# SparkFun_GPS_RTK_Surveyor_-_Enclosure.net
KiCad netlist of a schematic drawn in EAGLE
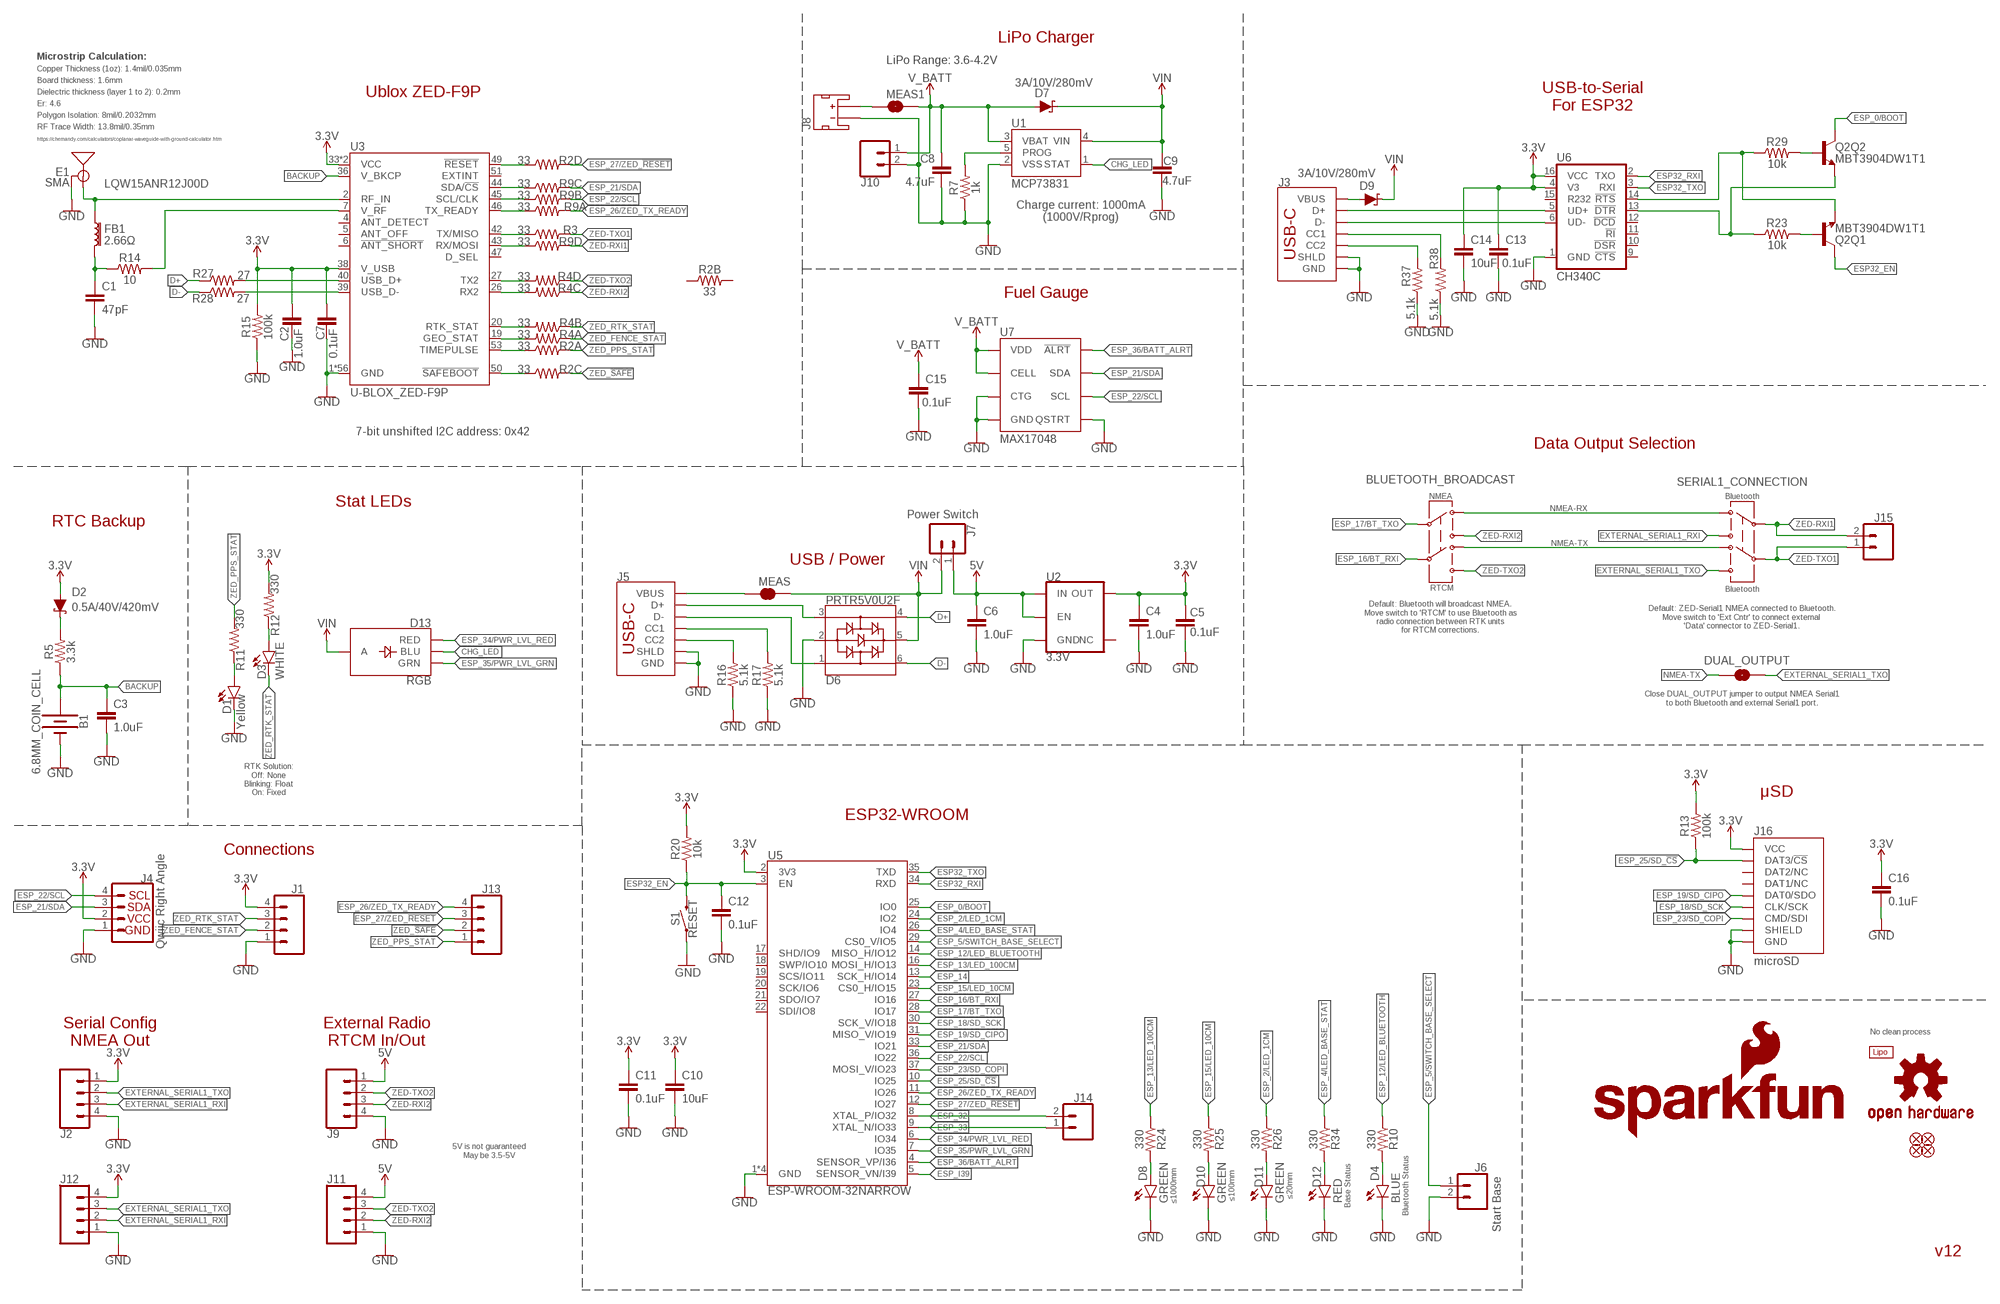
[diagram p0: schematic, sheet 1]

(export (version "E")
  (design (tool "Eeschema 10.0.6"))
  (components
    (comp (ref "B1")
      (value "6.8MM_COIN_CELL")
      (footprint "eagle-import:ML414H_IV01E")
      (libsource (lib "eagle-import") (part "ML414H_IV01E_BATTERY"))
    )
    (comp (ref "BLUETOOTH_BROADCAST")
      (value "SWITCH-DPDT-SMD-AYZ0202")
      (footprint "eagle-import:SWITCH_DPDT_SMD_AYZ0202")
      (libsource (lib "eagle-import") (part "SWITCH-DPDT-SMD-AYZ0202"))
    )
    (comp (ref "BT1")
      (value "LIPO-OUTLINE1100")
      (footprint "eagle-import:LIPO-1000")
      (libsource (lib "eagle-import") (part "LIPO-OUTLINE1100"))
    )
    (comp (ref "C1")
      (value "47pF")
      (footprint "eagle-import:0402")
      (libsource (lib "eagle-import") (part "47PF-0402-25V-5%-X7R"))
    )
    (comp (ref "C2")
      (value "1.0uF")
      (footprint "eagle-import:0603")
      (libsource (lib "eagle-import") (part "1.0UF-0603-16V-10%-X7R"))
    )
    (comp (ref "C3")
      (value "1.0uF")
      (footprint "eagle-import:0603")
      (libsource (lib "eagle-import") (part "1.0UF-0603-16V-10%-X7R"))
    )
    (comp (ref "C4")
      (value "1.0uF")
      (footprint "eagle-import:0603")
      (libsource (lib "eagle-import") (part "1.0UF-0603-16V-10%-X7R"))
    )
    (comp (ref "C5")
      (value "0.1uF")
      (footprint "eagle-import:0603")
      (libsource (lib "eagle-import") (part "0.1UF-0603-25V-5%"))
    )
    (comp (ref "C6")
      (value "1.0uF")
      (footprint "eagle-import:0603")
      (libsource (lib "eagle-import") (part "1.0UF-0603-16V-10%-X7R"))
    )
    (comp (ref "C7")
      (value "0.1uF")
      (footprint "eagle-import:0603")
      (libsource (lib "eagle-import") (part "0.1UF-0603-25V-5%"))
    )
    (comp (ref "C8")
      (value "4.7uF")
      (footprint "eagle-import:0603")
      (libsource (lib "eagle-import") (part "4.7UF-0603-35V-(20%)"))
    )
    (comp (ref "C9")
      (value "4.7uF")
      (footprint "eagle-import:0603")
      (libsource (lib "eagle-import") (part "4.7UF-0603-35V-(20%)"))
    )
    (comp (ref "C10")
      (value "10uF")
      (footprint "eagle-import:0603")
      (libsource (lib "eagle-import") (part "10UF-0603-6.3V-20%"))
    )
    (comp (ref "C11")
      (value "0.1uF")
      (footprint "eagle-import:0603")
      (libsource (lib "eagle-import") (part "0.1UF-0603-25V-(+80/-20%)"))
    )
    (comp (ref "C12")
      (value "0.1uF")
      (footprint "eagle-import:0603")
      (libsource (lib "eagle-import") (part "0.1UF-0603-25V-(+80/-20%)"))
    )
    (comp (ref "C13")
      (value "0.1uF")
      (footprint "eagle-import:0603")
      (libsource (lib "eagle-import") (part "0.1UF-0603-25V-(+80/-20%)"))
    )
    (comp (ref "C14")
      (value "10uF")
      (footprint "eagle-import:0603")
      (libsource (lib "eagle-import") (part "10UF-0603-6.3V-20%"))
    )
    (comp (ref "C15")
      (value "0.1uF")
      (footprint "eagle-import:0603")
      (libsource (lib "eagle-import") (part "0.1UF-0603-25V-(+80/-20%)"))
    )
    (comp (ref "C16")
      (value "0.1uF")
      (footprint "eagle-import:0603")
      (libsource (lib "eagle-import") (part "0.1UF-0603-25V-(+80/-20%)"))
    )
    (comp (ref "D1")
      (value "Yellow")
      (footprint "eagle-import:LED-0603")
      (libsource (lib "eagle-import") (part "LED-YELLOW0603"))
    )
    (comp (ref "D2")
      (value "0.5A/40V/420mV")
      (footprint "eagle-import:SOD-323")
      (libsource (lib "eagle-import") (part "DIODE-SCHOTTKY-PMEG4005EJ"))
    )
    (comp (ref "D3")
      (value "WHITE")
      (footprint "eagle-import:LED-0603")
      (libsource (lib "eagle-import") (part "LED-WHITE0603"))
    )
    (comp (ref "D4")
      (value "BLUE")
      (footprint "eagle-import:LED-0603")
      (libsource (lib "eagle-import") (part "LED-BLUE0603"))
    )
    (comp (ref "D6")
      (value "PRTR5V0U2F")
      (footprint "eagle-import:SOT886")
      (libsource (lib "eagle-import") (part "PRTR5V0U2F"))
    )
    (comp (ref "D7")
      (value "3A/10V/280mV")
      (footprint "eagle-import:SOD-323")
      (libsource (lib "eagle-import") (part "DIODE-SCHOTTKY-BAT60A"))
    )
    (comp (ref "D8")
      (value "GREEN")
      (footprint "eagle-import:LED-0603")
      (libsource (lib "eagle-import") (part "LED-GREEN0603"))
    )
    (comp (ref "D9")
      (value "3A/10V/280mV")
      (footprint "eagle-import:SOD-323")
      (libsource (lib "eagle-import") (part "DIODE-SCHOTTKY-BAT60A"))
    )
    (comp (ref "D10")
      (value "GREEN")
      (footprint "eagle-import:LED-0603")
      (libsource (lib "eagle-import") (part "LED-GREEN0603"))
    )
    (comp (ref "D11")
      (value "GREEN")
      (footprint "eagle-import:LED-0603")
      (libsource (lib "eagle-import") (part "LED-GREEN0603"))
    )
    (comp (ref "D12")
      (value "RED")
      (footprint "eagle-import:LED-0603")
      (libsource (lib "eagle-import") (part "LED-RED0603"))
    )
    (comp (ref "D13")
      (value "RGB")
      (footprint "eagle-import:P-LCC-4-3")
      (libsource (lib "eagle-import") (part "LED-RGB-CAPLCC"))
    )
    (comp (ref "DUAL_OUTPUT")
      (value "JUMPER-SMT_2_NO_SILK")
      (footprint "eagle-import:SMT-JUMPER_2_NO_SILK")
      (libsource (lib "eagle-import") (part "JUMPER-SMT_2_NO_SILK"))
    )
    (comp (ref "E1")
      (value "SMA")
      (footprint "eagle-import:SMA-EDGE-SMD")
      (libsource (lib "eagle-import") (part "ANTENNA-GROUNDEDEDGE_SMA_SMD"))
    )
    (comp (ref "FB1")
      (value "2.66Ω")
      (footprint "eagle-import:0402-TIGHT")
      (libsource (lib "eagle-import") (part "FERRITE_BEAD-0402-2.66OHM-1GHZ"))
    )
    (comp (ref "J1")
      (value "CONN_041X04_NO_SILK_NO_POP")
      (footprint "eagle-import:1X04_NO_SILK")
      (libsource (lib "eagle-import") (part "CONN_041X04_NO_SILK_NO_POP"))
    )
    (comp (ref "J2")
      (value "CONN_04JST-SMD-LOCKING")
      (footprint "eagle-import:JST-4-SMD-1.25MM-LOCKING")
      (libsource (lib "eagle-import") (part "CONN_04JST-SMD-LOCKING"))
    )
    (comp (ref "J3")
      (value "USB-C")
      (footprint "eagle-import:USB-C-16P-2LAYER-PADS")
      (libsource (lib "eagle-import") (part "USB_C_2-LAYER_PADS"))
    )
    (comp (ref "J4")
      (value "Qwiic Right Angle")
      (footprint "eagle-import:JST04_1MM_RA")
      (libsource (lib "eagle-import") (part "I2C_STANDARDQWIIC"))
    )
    (comp (ref "J5")
      (value "USB_C_2-LAYER_PADS")
      (footprint "eagle-import:USB-C-16P-2LAYER-PADS")
      (libsource (lib "eagle-import") (part "USB_C_2-LAYER_PADS"))
    )
    (comp (ref "J6")
      (value "Start Base")
      (footprint "eagle-import:JST-2-SMD")
      (libsource (lib "eagle-import") (part "CONN_02-JST-2MM-SMT"))
    )
    (comp (ref "J7")
      (value "Power Switch")
      (footprint "eagle-import:JST-2-SMD")
      (libsource (lib "eagle-import") (part "CONN_02-JST-2MM-SMT"))
    )
    (comp (ref "J8")
      (value "JST_2MM_MALE")
      (footprint "eagle-import:JST-2-SMD")
      (libsource (lib "eagle-import") (part "JST_2MM_MALE"))
    )
    (comp (ref "J9")
      (value "CONN_04JST-SMD-LOCKING")
      (footprint "eagle-import:JST-4-SMD-1.25MM-LOCKING")
      (libsource (lib "eagle-import") (part "CONN_04JST-SMD-LOCKING"))
    )
    (comp (ref "J10")
      (value "CONN_021X02_NO_SILK")
      (footprint "eagle-import:1X02_NO_SILK")
      (libsource (lib "eagle-import") (part "CONN_021X02_NO_SILK"))
    )
    (comp (ref "J11")
      (value "CONN_041X04_NO_SILK_NO_POP")
      (footprint "eagle-import:1X04_NO_SILK")
      (libsource (lib "eagle-import") (part "CONN_041X04_NO_SILK_NO_POP"))
    )
    (comp (ref "J12")
      (value "CONN_041X04_NO_SILK_NO_POP")
      (footprint "eagle-import:1X04_NO_SILK")
      (libsource (lib "eagle-import") (part "CONN_041X04_NO_SILK_NO_POP"))
    )
    (comp (ref "J13")
      (value "CONN_041X04_NO_SILK_NO_POP")
      (footprint "eagle-import:1X04_NO_SILK")
      (libsource (lib "eagle-import") (part "CONN_041X04_NO_SILK_NO_POP"))
    )
    (comp (ref "J14")
      (value "CONN_021X02_NO_SILK")
      (footprint "eagle-import:1X02_NO_SILK")
      (libsource (lib "eagle-import") (part "CONN_021X02_NO_SILK"))
    )
    (comp (ref "J15")
      (value "CONN_021X02_NO_SILK")
      (footprint "eagle-import:1X02_NO_SILK")
      (libsource (lib "eagle-import") (part "CONN_021X02_NO_SILK"))
    )
    (comp (ref "J16")
      (value "microSD")
      (footprint "eagle-import:MICRO-SD-SOCKET")
      (libsource (lib "eagle-import") (part "MICRO-SD-SDIOPUSH-PUSH"))
    )
    (comp (ref "JP21")
      (value "FIDUCIALUFIDUCIAL")
      (footprint "eagle-import:FIDUCIAL-MICRO")
      (libsource (lib "eagle-import") (part "FIDUCIALUFIDUCIAL"))
    )
    (comp (ref "JP61")
      (value "FIDUCIALUFIDUCIAL")
      (footprint "eagle-import:FIDUCIAL-MICRO")
      (libsource (lib "eagle-import") (part "FIDUCIALUFIDUCIAL"))
    )
    (comp (ref "JP71")
      (value "FIDUCIALUFIDUCIAL")
      (footprint "eagle-import:FIDUCIAL-MICRO")
      (libsource (lib "eagle-import") (part "FIDUCIALUFIDUCIAL"))
    )
    (comp (ref "JP81")
      (value "FIDUCIALUFIDUCIAL")
      (footprint "eagle-import:FIDUCIAL-MICRO")
      (libsource (lib "eagle-import") (part "FIDUCIALUFIDUCIAL"))
    )
    (comp (ref "LOGO1")
      (value "OSHW-LOGOMINI")
      (footprint "eagle-import:OSHW-LOGO-MINI")
      (libsource (lib "eagle-import") (part "OSHW-LOGOMINI"))
    )
    (comp (ref "LOGO2")
      (value "SFE_LOGO_NAME_FLAME.1_INCH")
      (footprint "eagle-import:SFE_LOGO_NAME_FLAME_.1")
      (libsource (lib "eagle-import") (part "SFE_LOGO_NAME_FLAME.1_INCH"))
    )
    (comp (ref "MEAS")
      (value "JUMPER-COMBO_2_NC_TRACE")
      (footprint "eagle-import:COMBO-JUMPER_2_NC_TRACE")
      (libsource (lib "eagle-import") (part "JUMPER-COMBO_2_NC_TRACE"))
    )
    (comp (ref "MEAS1")
      (value "JUMPER-COMBO_2_NC_TRACE")
      (footprint "eagle-import:COMBO-JUMPER_2_NC_TRACE")
      (libsource (lib "eagle-import") (part "JUMPER-COMBO_2_NC_TRACE"))
    )
    (comp (ref "Q2")
      (value "MBT3904DW1T1")
      (footprint "eagle-import:SC70-6")
      (libsource (lib "eagle-import") (part "TRANS_NPN_DUAL-MBT3904DW1T1"))
    )
    (comp (ref "R2")
      (value "33")
      (footprint "eagle-import:1206_RA")
      (libsource (lib "eagle-import") (part "33OHM_RA-1206-1/16W-5%"))
    )
    (comp (ref "R3")
      (value "33")
      (footprint "eagle-import:0603")
      (libsource (lib "eagle-import") (part "33OHM-0603-1/10W-1%"))
    )
    (comp (ref "R4")
      (value "33")
      (footprint "eagle-import:1206_RA")
      (libsource (lib "eagle-import") (part "33OHM_RA-1206-1/16W-5%"))
    )
    (comp (ref "R5")
      (value "3.3k")
      (footprint "eagle-import:0603")
      (libsource (lib "eagle-import") (part "3.3KOHM-0603-1/10W-1%"))
    )
    (comp (ref "R7")
      (value "1k")
      (footprint "eagle-import:0603")
      (libsource (lib "eagle-import") (part "1KOHM-0603-1/10W-1%"))
    )
    (comp (ref "R9")
      (value "33")
      (footprint "eagle-import:1206_RA")
      (libsource (lib "eagle-import") (part "33OHM_RA-1206-1/16W-5%"))
    )
    (comp (ref "R10")
      (value "330")
      (footprint "eagle-import:0603")
      (libsource (lib "eagle-import") (part "330OHM-0603-1/10W-1%"))
    )
    (comp (ref "R11")
      (value "330")
      (footprint "eagle-import:0603")
      (libsource (lib "eagle-import") (part "330OHM-0603-1/10W-1%"))
    )
    (comp (ref "R12")
      (value "330")
      (footprint "eagle-import:0603")
      (libsource (lib "eagle-import") (part "330OHM-0603-1/10W-1%"))
    )
    (comp (ref "R13")
      (value "100k")
      (footprint "eagle-import:0603")
      (libsource (lib "eagle-import") (part "100KOHM-0603-1/10W-1%"))
    )
    (comp (ref "R14")
      (value "10")
      (footprint "eagle-import:0603")
      (libsource (lib "eagle-import") (part "10OHM-0603-1/10W-1%"))
    )
    (comp (ref "R15")
      (value "100k")
      (footprint "eagle-import:0603")
      (libsource (lib "eagle-import") (part "100KOHM-0603-1/10W-1%"))
    )
    (comp (ref "R16")
      (value "5.1k")
      (footprint "eagle-import:0603")
      (libsource (lib "eagle-import") (part "5.1KOHM5.1KOHM-0603-1/10W-1%"))
    )
    (comp (ref "R17")
      (value "5.1k")
      (footprint "eagle-import:0603")
      (libsource (lib "eagle-import") (part "5.1KOHM5.1KOHM-0603-1/10W-1%"))
    )
    (comp (ref "R20")
      (value "10k")
      (footprint "eagle-import:0603")
      (libsource (lib "eagle-import") (part "10KOHM-0603-1/10W-1%"))
    )
    (comp (ref "R23")
      (value "10k")
      (footprint "eagle-import:0603")
      (libsource (lib "eagle-import") (part "10KOHM-0603-1/10W-1%"))
    )
    (comp (ref "R24")
      (value "330")
      (footprint "eagle-import:0603")
      (libsource (lib "eagle-import") (part "330OHM-0603-1/10W-1%"))
    )
    (comp (ref "R25")
      (value "330")
      (footprint "eagle-import:0603")
      (libsource (lib "eagle-import") (part "330OHM-0603-1/10W-1%"))
    )
    (comp (ref "R26")
      (value "330")
      (footprint "eagle-import:0603")
      (libsource (lib "eagle-import") (part "330OHM-0603-1/10W-1%"))
    )
    (comp (ref "R27")
      (value "27")
      (footprint "eagle-import:0603")
      (libsource (lib "eagle-import") (part "27OHM-0603-1/10W-1%"))
    )
    (comp (ref "R28")
      (value "27")
      (footprint "eagle-import:0603")
      (libsource (lib "eagle-import") (part "27OHM-0603-1/10W-1%"))
    )
    (comp (ref "R29")
      (value "10k")
      (footprint "eagle-import:0603")
      (libsource (lib "eagle-import") (part "10KOHM-0603-1/10W-1%"))
    )
    (comp (ref "R34")
      (value "330")
      (footprint "eagle-import:0603")
      (libsource (lib "eagle-import") (part "330OHM-0603-1/10W-1%"))
    )
    (comp (ref "R37")
      (value "5.1k")
      (footprint "eagle-import:0603")
      (libsource (lib "eagle-import") (part "5.1KOHM5.1KOHM-0603-1/10W-1%"))
    )
    (comp (ref "R38")
      (value "5.1k")
      (footprint "eagle-import:0603")
      (libsource (lib "eagle-import") (part "5.1KOHM5.1KOHM-0603-1/10W-1%"))
    )
    (comp (ref "S1")
      (value "RESET")
      (footprint "eagle-import:TACTILE_SWITCH_SMD_5.2MM")
      (libsource (lib "eagle-import") (part "MOMENTARY-SWITCH-SPST-SMD-5.2-TALL-REDUNDANT"))
    )
    (comp (ref "SERIAL1_CONNECTION")
      (value "SWITCH-DPDT-SMD-AYZ0202")
      (footprint "eagle-import:SWITCH_DPDT_SMD_AYZ0202")
      (libsource (lib "eagle-import") (part "SWITCH-DPDT-SMD-AYZ0202"))
    )
    (comp (ref "U1")
      (value "MCP73831")
      (footprint "eagle-import:SOT23-5")
      (libsource (lib "eagle-import") (part "MCP73831"))
    )
    (comp (ref "U2")
      (value "3.3V")
      (footprint "eagle-import:SOT23-5")
      (libsource (lib "eagle-import") (part "V_REG_AP2112K-3.3V"))
    )
    (comp (ref "U3")
      (value "U-BLOX_ZED-F9P")
      (footprint "eagle-import:ZED-F9P")
      (libsource (lib "eagle-import") (part "U-BLOX_ZED-F9P"))
    )
    (comp (ref "U5")
      (value "ESP-WROOM-32NARROW")
      (footprint "eagle-import:ESP-WROOM-32-NARROW")
      (libsource (lib "eagle-import") (part "ESP-WROOM-32NARROW"))
    )
    (comp (ref "U6")
      (value "CH340C")
      (footprint "eagle-import:SO016")
      (libsource (lib "eagle-import") (part "CH340C"))
    )
    (comp (ref "U7")
      (value "MAX17048")
      (footprint "eagle-import:DFN-8")
      (libsource (lib "eagle-import") (part "MAX17048DFN8"))
    )
  )
  (nets
    (net (code "1") (name "3.3V") (class "Default")
      (node (ref "C10") (pin "1") (pinfunction "1_1") (pintype "passive"))
      (node (ref "C11") (pin "1") (pinfunction "1_1") (pintype "passive"))
      (node (ref "C13") (pin "1") (pinfunction "1_1") (pintype "passive"))
      (node (ref "C14") (pin "1") (pinfunction "1_1") (pintype "passive"))
      (node (ref "C16") (pin "1") (pinfunction "1_1") (pintype "passive"))
      (node (ref "C2") (pin "1") (pinfunction "1_1") (pintype "passive"))
      (node (ref "C4") (pin "1") (pinfunction "1_1") (pintype "passive"))
      (node (ref "C5") (pin "2") (pinfunction "2_2") (pintype "passive"))
      (node (ref "C7") (pin "2") (pinfunction "2_2") (pintype "passive"))
      (node (ref "D2") (pin "A") (pinfunction "A_A") (pintype "passive"))
      (node (ref "J1") (pin "4") (pinfunction "4_4") (pintype "passive"))
      (node (ref "J12") (pin "4") (pinfunction "4_4") (pintype "passive"))
      (node (ref "J16") (pin "VCC") (pinfunction "VCC_VCC") (pintype "bidirectional"))
      (node (ref "J2") (pin "1") (pinfunction "1_1") (pintype "passive"))
      (node (ref "J4") (pin "2") (pinfunction "2_2") (pintype "power_in"))
      (node (ref "R12") (pin "2") (pinfunction "2_2") (pintype "passive"))
      (node (ref "R13") (pin "2") (pinfunction "2_2") (pintype "passive"))
      (node (ref "R15") (pin "2") (pinfunction "2_2") (pintype "passive"))
      (node (ref "R20") (pin "2") (pinfunction "2_2") (pintype "passive"))
      (node (ref "U2") (pin "5") (pinfunction "OUT_5") (pintype "passive"))
      (node (ref "U3") (pin "33") (pinfunction "VCC_33") (pintype "bidirectional"))
      (node (ref "U3") (pin "34") (pinfunction "VCC_34") (pintype "bidirectional"))
      (node (ref "U3") (pin "38") (pinfunction "V_USB_38") (pintype "bidirectional"))
      (node (ref "U5") (pin "2") (pinfunction "3V3_2") (pintype "bidirectional"))
      (node (ref "U6") (pin "16") (pinfunction "VCC_16") (pintype "bidirectional"))
      (node (ref "U6") (pin "4") (pinfunction "V3_4") (pintype "bidirectional"))
    )
    (net (code "2") (name "5V") (class "Default")
      (node (ref "C6") (pin "1") (pinfunction "1_1") (pintype "passive"))
      (node (ref "J11") (pin "4") (pinfunction "4_4") (pintype "passive"))
      (node (ref "J7") (pin "1") (pinfunction "2_1") (pintype "passive"))
      (node (ref "J9") (pin "1") (pinfunction "1_1") (pintype "passive"))
      (node (ref "U2") (pin "1") (pinfunction "IN_1") (pintype "input"))
      (node (ref "U2") (pin "3") (pinfunction "EN_3") (pintype "input"))
    )
    (net (code "3") (name "BACKUP") (class "Default")
      (node (ref "B1") (pin "+") (pinfunction "+_+") (pintype "power_in"))
      (node (ref "C3") (pin "1") (pinfunction "1_1") (pintype "passive"))
      (node (ref "R5") (pin "1") (pinfunction "1_1") (pintype "passive"))
      (node (ref "U3") (pin "36") (pinfunction "V_BKCP_36") (pintype "bidirectional"))
    )
    (net (code "4") (name "CHG_LED") (class "Default")
      (node (ref "D13") (pin "3") (pinfunction "BLU_3") (pintype "bidirectional"))
      (node (ref "U1") (pin "1") (pinfunction "STAT_1") (pintype "output"))
    )
    (net (code "5") (name "D+") (class "Default")
      (node (ref "D6") (pin "4") (pinfunction "4_4") (pintype "bidirectional"))
      (node (ref "R27") (pin "1") (pinfunction "1_1") (pintype "passive"))
    )
    (net (code "6") (name "D-") (class "Default")
      (node (ref "D6") (pin "6") (pinfunction "6_6") (pintype "bidirectional"))
      (node (ref "R28") (pin "1") (pinfunction "1_1") (pintype "passive"))
    )
    (net (code "7") (name "ESP32_EN") (class "Default")
      (node (ref "C12") (pin "1") (pinfunction "1_1") (pintype "passive"))
      (node (ref "Q2") (pin "3") (pinfunction "C_3") (pintype "passive"))
      (node (ref "R20") (pin "1") (pinfunction "1_1") (pintype "passive"))
      (node (ref "S1") (pin "3") (pinfunction "2_3") (pintype "passive"))
      (node (ref "S1") (pin "4") (pinfunction "2_4") (pintype "passive"))
      (node (ref "U5") (pin "3") (pinfunction "EN_3") (pintype "bidirectional"))
    )
    (net (code "8") (name "ESP32_RXI") (class "Default")
      (node (ref "U5") (pin "34") (pinfunction "RXD_34") (pintype "bidirectional"))
      (node (ref "U6") (pin "2") (pinfunction "TXO_2") (pintype "bidirectional"))
    )
    (net (code "9") (name "ESP32_TXO") (class "Default")
      (node (ref "U5") (pin "35") (pinfunction "TXD_35") (pintype "bidirectional"))
      (node (ref "U6") (pin "3") (pinfunction "RXI_3") (pintype "bidirectional"))
    )
    (net (code "10") (name "ESP_0{slash}BOOT") (class "Default")
      (node (ref "Q2") (pin "6") (pinfunction "C_6") (pintype "passive"))
      (node (ref "U5") (pin "25") (pinfunction "IO0_25") (pintype "bidirectional"))
    )
    (net (code "11") (name "ESP_2{slash}LED_1CM") (class "Default")
      (node (ref "R26") (pin "1") (pinfunction "1_1") (pintype "passive"))
      (node (ref "U5") (pin "24") (pinfunction "IO2_24") (pintype "bidirectional"))
    )
    (net (code "12") (name "ESP_4{slash}LED_BASE_STAT") (class "Default")
      (node (ref "R34") (pin "1") (pinfunction "1_1") (pintype "passive"))
      (node (ref "U5") (pin "26") (pinfunction "IO4_26") (pintype "bidirectional"))
    )
    (net (code "13") (name "ESP_5{slash}SWITCH_BASE_SELECT") (class "Default")
      (node (ref "J6") (pin "1") (pinfunction "2_1") (pintype "passive"))
      (node (ref "U5") (pin "29") (pinfunction "CS0_V/IO5_29") (pintype "bidirectional"))
    )
    (net (code "14") (name "ESP_12{slash}LED_BLUETOOTH") (class "Default")
      (node (ref "R10") (pin "1") (pinfunction "1_1") (pintype "passive"))
      (node (ref "U5") (pin "14") (pinfunction "MISO_H/IO12_14") (pintype "bidirectional"))
    )
    (net (code "15") (name "ESP_13{slash}LED_100CM") (class "Default")
      (node (ref "R24") (pin "1") (pinfunction "1_1") (pintype "passive"))
      (node (ref "U5") (pin "16") (pinfunction "MOSI_H/IO13_16") (pintype "bidirectional"))
    )
    (net (code "16") (name "ESP_14") (class "Default")
      (node (ref "U5") (pin "13") (pinfunction "SCK_H/IO14_13") (pintype "bidirectional"))
    )
    (net (code "17") (name "ESP_15{slash}LED_10CM") (class "Default")
      (node (ref "R25") (pin "1") (pinfunction "1_1") (pintype "passive"))
      (node (ref "U5") (pin "23") (pinfunction "CS0_H/IO15_23") (pintype "bidirectional"))
    )
    (net (code "18") (name "ESP_16{slash}BT_RXI") (class "Default")
      (node (ref "BLUETOOTH_BROADCAST") (pin "5") (pinfunction "5_5") (pintype "bidirectional"))
      (node (ref "U5") (pin "27") (pinfunction "IO16_27") (pintype "bidirectional"))
    )
    (net (code "19") (name "ESP_17{slash}BT_TXO") (class "Default")
      (node (ref "BLUETOOTH_BROADCAST") (pin "2") (pinfunction "2_2") (pintype "bidirectional"))
      (node (ref "U5") (pin "28") (pinfunction "IO17_28") (pintype "bidirectional"))
    )
    (net (code "20") (name "ESP_18{slash}SD_SCK") (class "Default")
      (node (ref "J16") (pin "SCLK") (pinfunction "CLK/SCK_SCLK") (pintype "bidirectional"))
      (node (ref "U5") (pin "30") (pinfunction "SCK_V/IO18_30") (pintype "bidirectional"))
    )
    (net (code "21") (name "ESP_19{slash}SD_CIPO") (class "Default")
      (node (ref "J16") (pin "DO/DAT0") (pinfunction "DAT0/SDO_DO/DAT0") (pintype "bidirectional"))
      (node (ref "U5") (pin "31") (pinfunction "MISO_V/IO19_31") (pintype "bidirectional"))
    )
    (net (code "22") (name "ESP_21{slash}SDA") (class "Default")
      (node (ref "J4") (pin "3") (pinfunction "3_3") (pintype "passive"))
      (node (ref "R9") (pin "P6") (pinfunction "2_P6") (pintype "passive"))
      (node (ref "U5") (pin "33") (pinfunction "IO21_33") (pintype "bidirectional"))
      (node (ref "U7") (pin "8") (pinfunction "SDA_8") (pintype "input"))
    )
    (net (code "23") (name "ESP_22{slash}SCL") (class "Default")
      (node (ref "J4") (pin "4") (pinfunction "4_4") (pintype "passive"))
      (node (ref "R9") (pin "P7") (pinfunction "2_P7") (pintype "passive"))
      (node (ref "U5") (pin "36") (pinfunction "IO22_36") (pintype "bidirectional"))
      (node (ref "U7") (pin "7") (pinfunction "SCL_7") (pintype "output"))
    )
    (net (code "24") (name "ESP_23{slash}SD_COPI") (class "Default")
      (node (ref "J16") (pin "DI/CMD") (pinfunction "CMD/SDI_DI/CMD") (pintype "bidirectional"))
      (node (ref "U5") (pin "37") (pinfunction "MOSI_V/IO23_37") (pintype "bidirectional"))
    )
    (net (code "25") (name "ESP_25{slash}SD_~{CS}") (class "Default")
      (node (ref "J16") (pin "CS/DAT3") (pinfunction "DAT3/~{CS}_CS/DAT3") (pintype "bidirectional"))
      (node (ref "R13") (pin "1") (pinfunction "1_1") (pintype "passive"))
      (node (ref "U5") (pin "10") (pinfunction "IO25_10") (pintype "bidirectional"))
    )
    (net (code "26") (name "ESP_26{slash}ZED_TX_READY") (class "Default")
      (node (ref "J13") (pin "4") (pinfunction "4_4") (pintype "passive"))
      (node (ref "R9") (pin "P8") (pinfunction "2_P8") (pintype "passive"))
      (node (ref "U5") (pin "11") (pinfunction "IO26_11") (pintype "bidirectional"))
    )
    (net (code "27") (name "ESP_27{slash}ZED_~{RESET}") (class "Default")
      (node (ref "J13") (pin "3") (pinfunction "3_3") (pintype "passive"))
      (node (ref "R2") (pin "P5") (pinfunction "2_P5") (pintype "passive"))
      (node (ref "U5") (pin "12") (pinfunction "IO27_12") (pintype "bidirectional"))
    )
    (net (code "28") (name "ESP_32") (class "Default")
      (node (ref "J14") (pin "2") (pinfunction "2_2") (pintype "passive"))
      (node (ref "U5") (pin "8") (pinfunction "XTAL_P/IO32_8") (pintype "bidirectional"))
    )
    (net (code "29") (name "ESP_33") (class "Default")
      (node (ref "J14") (pin "1") (pinfunction "1_1") (pintype "passive"))
      (node (ref "U5") (pin "9") (pinfunction "XTAL_N/IO33_9") (pintype "bidirectional"))
    )
    (net (code "30") (name "ESP_34{slash}PWR_LVL_RED") (class "Default")
      (node (ref "D13") (pin "1") (pinfunction "RED_1") (pintype "bidirectional"))
      (node (ref "U5") (pin "6") (pinfunction "IO34_6") (pintype "bidirectional"))
    )
    (net (code "31") (name "ESP_35{slash}PWR_LVL_GRN") (class "Default")
      (node (ref "D13") (pin "2") (pinfunction "GRN_2") (pintype "bidirectional"))
      (node (ref "U5") (pin "7") (pinfunction "IO35_7") (pintype "bidirectional"))
    )
    (net (code "32") (name "ESP_36{slash}BATT_ALRT") (class "Default")
      (node (ref "U5") (pin "4") (pinfunction "SENSOR_VP/I36_4") (pintype "bidirectional"))
      (node (ref "U7") (pin "5") (pinfunction "~{ALRT}_5") (pintype "bidirectional"))
    )
    (net (code "33") (name "ESP_I39") (class "Default")
      (node (ref "U5") (pin "5") (pinfunction "SENSOR_VN/I39_5") (pintype "bidirectional"))
    )
    (net (code "34") (name "EXTERNAL_SERIAL1_RXI") (class "Default")
      (node (ref "J12") (pin "2") (pinfunction "2_2") (pintype "passive"))
      (node (ref "J2") (pin "3") (pinfunction "3_3") (pintype "passive"))
      (node (ref "SERIAL1_CONNECTION") (pin "3") (pinfunction "3_3") (pintype "bidirectional"))
    )
    (net (code "35") (name "EXTERNAL_SERIAL1_TXO") (class "Default")
      (node (ref "DUAL_OUTPUT") (pin "2") (pinfunction "2_2") (pintype "passive"))
      (node (ref "J12") (pin "3") (pinfunction "3_3") (pintype "passive"))
      (node (ref "J2") (pin "2") (pinfunction "2_2") (pintype "passive"))
      (node (ref "SERIAL1_CONNECTION") (pin "6") (pinfunction "6_6") (pintype "bidirectional"))
    )
    (net (code "36") (name "GND") (class "Default")
      (node (ref "B1") (pin "-") (pinfunction "-_-") (pintype "power_in"))
      (node (ref "C1") (pin "2") (pinfunction "2_2") (pintype "passive"))
      (node (ref "C10") (pin "2") (pinfunction "2_2") (pintype "passive"))
      (node (ref "C11") (pin "2") (pinfunction "2_2") (pintype "passive"))
      (node (ref "C12") (pin "2") (pinfunction "2_2") (pintype "passive"))
      (node (ref "C13") (pin "2") (pinfunction "2_2") (pintype "passive"))
      (node (ref "C14") (pin "2") (pinfunction "2_2") (pintype "passive"))
      (node (ref "C15") (pin "2") (pinfunction "2_2") (pintype "passive"))
      (node (ref "C16") (pin "2") (pinfunction "2_2") (pintype "passive"))
      (node (ref "C2") (pin "2") (pinfunction "2_2") (pintype "passive"))
      (node (ref "C3") (pin "2") (pinfunction "2_2") (pintype "passive"))
      (node (ref "C4") (pin "2") (pinfunction "2_2") (pintype "passive"))
      (node (ref "C5") (pin "1") (pinfunction "1_1") (pintype "passive"))
      (node (ref "C6") (pin "2") (pinfunction "2_2") (pintype "passive"))
      (node (ref "C7") (pin "1") (pinfunction "1_1") (pintype "passive"))
      (node (ref "C8") (pin "2") (pinfunction "2_2") (pintype "passive"))
      (node (ref "C9") (pin "2") (pinfunction "2_2") (pintype "passive"))
      (node (ref "D1") (pin "C") (pinfunction "C_C") (pintype "passive"))
      (node (ref "D10") (pin "C") (pinfunction "C_C") (pintype "passive"))
      (node (ref "D11") (pin "C") (pinfunction "C_C") (pintype "passive"))
      (node (ref "D12") (pin "C") (pinfunction "C_C") (pintype "passive"))
      (node (ref "D4") (pin "C") (pinfunction "C_C") (pintype "passive"))
      (node (ref "D6") (pin "2") (pinfunction "2_2") (pintype "bidirectional"))
      (node (ref "D8") (pin "C") (pinfunction "C_C") (pintype "passive"))
      (node (ref "E1") (pin "GND@0") (pinfunction "GND_GND@0") (pintype "bidirectional"))
      (node (ref "E1") (pin "GND@1") (pinfunction "GND_GND@1") (pintype "bidirectional"))
      (node (ref "J1") (pin "1") (pinfunction "1_1") (pintype "passive"))
      (node (ref "J10") (pin "2") (pinfunction "2_2") (pintype "passive"))
      (node (ref "J11") (pin "1") (pinfunction "1_1") (pintype "passive"))
      (node (ref "J12") (pin "1") (pinfunction "1_1") (pintype "passive"))
      (node (ref "J16") (pin "CD1") (pinfunction "SHIELD_CD1") (pintype "bidirectional"))
      (node (ref "J16") (pin "GND") (pinfunction "GND_GND") (pintype "bidirectional"))
      (node (ref "J16") (pin "GND1") (pinfunction "GND_GND1") (pintype "bidirectional"))
      (node (ref "J16") (pin "GND3") (pinfunction "GND_GND3") (pintype "bidirectional"))
      (node (ref "J2") (pin "4") (pinfunction "4_4") (pintype "passive"))
      (node (ref "J3") (pin "GND") (pinfunction "GND_GND") (pintype "bidirectional"))
      (node (ref "J3") (pin "GND2") (pinfunction "GND_GND2") (pintype "bidirectional"))
      (node (ref "J3") (pin "SHLD1") (pinfunction "SHLD_SHLD1") (pintype "bidirectional"))
      (node (ref "J3") (pin "SHLD2") (pinfunction "SHLD_SHLD2") (pintype "bidirectional"))
      (node (ref "J3") (pin "SHLD3") (pinfunction "SHLD_SHLD3") (pintype "bidirectional"))
      (node (ref "J3") (pin "SHLD4") (pinfunction "SHLD_SHLD4") (pintype "bidirectional"))
      (node (ref "J4") (pin "1") (pinfunction "1_1") (pintype "power_in"))
      (node (ref "J5") (pin "GND") (pinfunction "GND_GND") (pintype "bidirectional"))
      (node (ref "J5") (pin "GND2") (pinfunction "GND_GND2") (pintype "bidirectional"))
      (node (ref "J5") (pin "SHLD1") (pinfunction "SHLD_SHLD1") (pintype "bidirectional"))
      (node (ref "J5") (pin "SHLD2") (pinfunction "SHLD_SHLD2") (pintype "bidirectional"))
      (node (ref "J5") (pin "SHLD3") (pinfunction "SHLD_SHLD3") (pintype "bidirectional"))
      (node (ref "J5") (pin "SHLD4") (pinfunction "SHLD_SHLD4") (pintype "bidirectional"))
      (node (ref "J6") (pin "2") (pinfunction "1_2") (pintype "passive"))
      (node (ref "J8") (pin "1") (pinfunction "-_1") (pintype "bidirectional"))
      (node (ref "J9") (pin "4") (pinfunction "4_4") (pintype "passive"))
      (node (ref "R15") (pin "1") (pinfunction "1_1") (pintype "passive"))
      (node (ref "R16") (pin "1") (pinfunction "1_1") (pintype "passive"))
      (node (ref "R17") (pin "1") (pinfunction "1_1") (pintype "passive"))
      (node (ref "R37") (pin "1") (pinfunction "1_1") (pintype "passive"))
      (node (ref "R38") (pin "1") (pinfunction "1_1") (pintype "passive"))
      (node (ref "R7") (pin "1") (pinfunction "1_1") (pintype "passive"))
      (node (ref "S1") (pin "1") (pinfunction "1_1") (pintype "passive"))
      (node (ref "S1") (pin "2") (pinfunction "1_2") (pintype "passive"))
      (node (ref "U1") (pin "2") (pinfunction "VSS_2") (pintype "power_in"))
      (node (ref "U2") (pin "2") (pinfunction "GND_2") (pintype "input"))
      (node (ref "U3") (pin "1") (pinfunction "GND_1") (pintype "bidirectional"))
      (node (ref "U3") (pin "100") (pinfunction "GND_100") (pintype "bidirectional"))
      (node (ref "U3") (pin "101") (pinfunction "GND_101") (pintype "bidirectional"))
      (node (ref "U3") (pin "102") (pinfunction "GND_102") (pintype "bidirectional"))
      (node (ref "U3") (pin "12") (pinfunction "GND_12") (pintype "bidirectional"))
      (node (ref "U3") (pin "14") (pinfunction "GND_14") (pintype "bidirectional"))
      (node (ref "U3") (pin "3") (pinfunction "GND_3") (pintype "bidirectional"))
      (node (ref "U3") (pin "32") (pinfunction "GND_32") (pintype "bidirectional"))
      (node (ref "U3") (pin "37") (pinfunction "GND_37") (pintype "bidirectional"))
      (node (ref "U3") (pin "41") (pinfunction "GND_41") (pintype "bidirectional"))
      (node (ref "U3") (pin "48") (pinfunction "GND_48") (pintype "bidirectional"))
      (node (ref "U3") (pin "55") (pinfunction "GND_55") (pintype "bidirectional"))
      (node (ref "U3") (pin "56") (pinfunction "GND_56") (pintype "bidirectional"))
      (node (ref "U3") (pin "57") (pinfunction "GND_57") (pintype "bidirectional"))
      (node (ref "U3") (pin "58") (pinfunction "GND_58") (pintype "bidirectional"))
      (node (ref "U3") (pin "59") (pinfunction "GND_59") (pintype "bidirectional"))
      (node (ref "U3") (pin "60") (pinfunction "GND_60") (pintype "bidirectional"))
      (node (ref "U3") (pin "61") (pinfunction "GND_61") (pintype "bidirectional"))
      (node (ref "U3") (pin "62") (pinfunction "GND_62") (pintype "bidirectional"))
      (node (ref "U3") (pin "63") (pinfunction "GND_63") (pintype "bidirectional"))
      (node (ref "U3") (pin "64") (pinfunction "GND_64") (pintype "bidirectional"))
      (node (ref "U3") (pin "65") (pinfunction "GND_65") (pintype "bidirectional"))
      (node (ref "U3") (pin "66") (pinfunction "GND_66") (pintype "bidirectional"))
      (node (ref "U3") (pin "67") (pinfunction "GND_67") (pintype "bidirectional"))
      (node (ref "U3") (pin "68") (pinfunction "GND_68") (pintype "bidirectional"))
      (node (ref "U3") (pin "69") (pinfunction "GND_69") (pintype "bidirectional"))
      (node (ref "U3") (pin "70") (pinfunction "GND_70") (pintype "bidirectional"))
      (node (ref "U3") (pin "71") (pinfunction "GND_71") (pintype "bidirectional"))
      (node (ref "U3") (pin "72") (pinfunction "GND_72") (pintype "bidirectional"))
      (node (ref "U3") (pin "73") (pinfunction "GND_73") (pintype "bidirectional"))
      (node (ref "U3") (pin "74") (pinfunction "GND_74") (pintype "bidirectional"))
      (node (ref "U3") (pin "75") (pinfunction "GND_75") (pintype "bidirectional"))
      (node (ref "U3") (pin "76") (pinfunction "GND_76") (pintype "bidirectional"))
      (node (ref "U3") (pin "77") (pinfunction "GND_77") (pintype "bidirectional"))
      (node (ref "U3") (pin "78") (pinfunction "GND_78") (pintype "bidirectional"))
      (node (ref "U3") (pin "79") (pinfunction "GND_79") (pintype "bidirectional"))
      (node (ref "U3") (pin "80") (pinfunction "GND_80") (pintype "bidirectional"))
      (node (ref "U3") (pin "81") (pinfunction "GND_81") (pintype "bidirectional"))
      (node (ref "U3") (pin "82") (pinfunction "GND_82") (pintype "bidirectional"))
      (node (ref "U3") (pin "83") (pinfunction "GND_83") (pintype "bidirectional"))
      (node (ref "U3") (pin "84") (pinfunction "GND_84") (pintype "bidirectional"))
      (node (ref "U3") (pin "85") (pinfunction "GND_85") (pintype "bidirectional"))
      (node (ref "U3") (pin "86") (pinfunction "GND_86") (pintype "bidirectional"))
      (node (ref "U3") (pin "87") (pinfunction "GND_87") (pintype "bidirectional"))
      (node (ref "U3") (pin "88") (pinfunction "GND_88") (pintype "bidirectional"))
      (node (ref "U3") (pin "89") (pinfunction "GND_89") (pintype "bidirectional"))
      (node (ref "U3") (pin "90") (pinfunction "GND_90") (pintype "bidirectional"))
      (node (ref "U3") (pin "91") (pinfunction "GND_91") (pintype "bidirectional"))
      (node (ref "U3") (pin "92") (pinfunction "GND_92") (pintype "bidirectional"))
      (node (ref "U3") (pin "93") (pinfunction "GND_93") (pintype "bidirectional"))
      (node (ref "U3") (pin "94") (pinfunction "GND_94") (pintype "bidirectional"))
      (node (ref "U3") (pin "95") (pinfunction "GND_95") (pintype "bidirectional"))
      (node (ref "U3") (pin "96") (pinfunction "GND_96") (pintype "bidirectional"))
      (node (ref "U3") (pin "97") (pinfunction "GND_97") (pintype "bidirectional"))
      (node (ref "U3") (pin "98") (pinfunction "GND_98") (pintype "bidirectional"))
      (node (ref "U3") (pin "99") (pinfunction "GND_99") (pintype "bidirectional"))
      (node (ref "U5") (pin "1") (pinfunction "GND_1") (pintype "bidirectional"))
      (node (ref "U5") (pin "15") (pinfunction "GND_15") (pintype "bidirectional"))
      (node (ref "U5") (pin "38") (pinfunction "GND_38") (pintype "bidirectional"))
      (node (ref "U5") (pin "GND") (pinfunction "GND_GND") (pintype "bidirectional"))
      (node (ref "U6") (pin "1") (pinfunction "GND_1") (pintype "bidirectional"))
      (node (ref "U7") (pin "1") (pinfunction "CTG_1") (pintype "input"))
      (node (ref "U7") (pin "4") (pinfunction "GND_4") (pintype "bidirectional"))
      (node (ref "U7") (pin "6") (pinfunction "QSTRT_6") (pintype "bidirectional"))
      (node (ref "U7") (pin "9") (pinfunction "GND_9") (pintype "bidirectional"))
    )
    (net (code "37") (name "NMEA-RX") (class "Default")
      (node (ref "BLUETOOTH_BROADCAST") (pin "1") (pinfunction "1_1") (pintype "bidirectional"))
      (node (ref "SERIAL1_CONNECTION") (pin "1") (pinfunction "1_1") (pintype "bidirectional"))
    )
    (net (code "38") (name "NMEA-TX") (class "Default")
      (node (ref "BLUETOOTH_BROADCAST") (pin "4") (pinfunction "4_4") (pintype "bidirectional"))
      (node (ref "DUAL_OUTPUT") (pin "1") (pinfunction "1_1") (pintype "passive"))
      (node (ref "SERIAL1_CONNECTION") (pin "4") (pinfunction "4_4") (pintype "bidirectional"))
    )
    (net (code "39") (name "Net-(C1-Pad1)") (class "Default")
      (node (ref "C1") (pin "1") (pinfunction "1_1") (pintype "passive"))
      (node (ref "FB1") (pin "2") (pinfunction "2_2") (pintype "passive"))
      (node (ref "R14") (pin "1") (pinfunction "1_1") (pintype "passive"))
    )
    (net (code "40") (name "Net-(D1-PadA)") (class "Default")
      (node (ref "D1") (pin "A") (pinfunction "A_A") (pintype "passive"))
      (node (ref "R11") (pin "1") (pinfunction "1_1") (pintype "passive"))
    )
    (net (code "41") (name "Net-(D2-PadC)") (class "Default")
      (node (ref "D2") (pin "C") (pinfunction "C_C") (pintype "passive"))
      (node (ref "R5") (pin "2") (pinfunction "2_2") (pintype "passive"))
    )
    (net (code "42") (name "Net-(D3-PadA)") (class "Default")
      (node (ref "D3") (pin "A") (pinfunction "A_A") (pintype "passive"))
      (node (ref "R12") (pin "1") (pinfunction "1_1") (pintype "passive"))
    )
    (net (code "43") (name "Net-(D4-PadA)") (class "Default")
      (node (ref "D4") (pin "A") (pinfunction "A_A") (pintype "passive"))
      (node (ref "R10") (pin "2") (pinfunction "2_2") (pintype "passive"))
    )
    (net (code "44") (name "Net-(D6-Pad1)") (class "Default")
      (node (ref "D6") (pin "1") (pinfunction "1_1") (pintype "bidirectional"))
      (node (ref "J5") (pin "A7") (pinfunction "D-_A7") (pintype "bidirectional"))
      (node (ref "J5") (pin "B7") (pinfunction "D-_B7") (pintype "bidirectional"))
    )
    (net (code "45") (name "Net-(D6-Pad3)") (class "Default")
      (node (ref "D6") (pin "3") (pinfunction "3_3") (pintype "bidirectional"))
      (node (ref "J5") (pin "A6") (pinfunction "D+_A6") (pintype "bidirectional"))
      (node (ref "J5") (pin "B6") (pinfunction "D+_B6") (pintype "bidirectional"))
    )
    (net (code "46") (name "Net-(D8-PadA)") (class "Default")
      (node (ref "D8") (pin "A") (pinfunction "A_A") (pintype "passive"))
      (node (ref "R24") (pin "2") (pinfunction "2_2") (pintype "passive"))
    )
    (net (code "47") (name "Net-(D9-PadA)") (class "Default")
      (node (ref "D9") (pin "A") (pinfunction "A_A") (pintype "passive"))
      (node (ref "J3") (pin "VBUS1") (pinfunction "VBUS_VBUS1") (pintype "bidirectional"))
      (node (ref "J3") (pin "VBUS2") (pinfunction "VBUS_VBUS2") (pintype "bidirectional"))
    )
    (net (code "48") (name "Net-(D10-PadA)") (class "Default")
      (node (ref "D10") (pin "A") (pinfunction "A_A") (pintype "passive"))
      (node (ref "R25") (pin "2") (pinfunction "2_2") (pintype "passive"))
    )
    (net (code "49") (name "Net-(D11-PadA)") (class "Default")
      (node (ref "D11") (pin "A") (pinfunction "A_A") (pintype "passive"))
      (node (ref "R26") (pin "2") (pinfunction "2_2") (pintype "passive"))
    )
    (net (code "50") (name "Net-(D12-PadA)") (class "Default")
      (node (ref "D12") (pin "A") (pinfunction "A_A") (pintype "passive"))
      (node (ref "R34") (pin "2") (pinfunction "2_2") (pintype "passive"))
    )
    (net (code "51") (name "Net-(E1-SIGNAL)") (class "Default")
      (node (ref "E1") (pin "SIG") (pinfunction "SIGNAL_SIG") (pintype "bidirectional"))
      (node (ref "FB1") (pin "1") (pinfunction "1_1") (pintype "passive"))
      (node (ref "U3") (pin "2") (pinfunction "RF_IN_2") (pintype "bidirectional"))
    )
    (net (code "52") (name "Net-(J3-CC1)") (class "Default")
      (node (ref "J3") (pin "A5") (pinfunction "CC1_A5") (pintype "bidirectional"))
      (node (ref "R38") (pin "2") (pinfunction "2_2") (pintype "passive"))
    )
    (net (code "53") (name "Net-(J3-CC2)") (class "Default")
      (node (ref "J3") (pin "B5") (pinfunction "CC2_B5") (pintype "bidirectional"))
      (node (ref "R37") (pin "2") (pinfunction "2_2") (pintype "passive"))
    )
    (net (code "54") (name "Net-(J5-CC1)") (class "Default")
      (node (ref "J5") (pin "A5") (pinfunction "CC1_A5") (pintype "bidirectional"))
      (node (ref "R17") (pin "2") (pinfunction "2_2") (pintype "passive"))
    )
    (net (code "55") (name "Net-(J5-CC2)") (class "Default")
      (node (ref "J5") (pin "B5") (pinfunction "CC2_B5") (pintype "bidirectional"))
      (node (ref "R16") (pin "2") (pinfunction "2_2") (pintype "passive"))
    )
    (net (code "56") (name "Net-(J5-VBUS-PadVBUS1)") (class "Default")
      (node (ref "J5") (pin "VBUS1") (pinfunction "VBUS_VBUS1") (pintype "bidirectional"))
      (node (ref "J5") (pin "VBUS2") (pinfunction "VBUS_VBUS2") (pintype "bidirectional"))
      (node (ref "MEAS") (pin "1") (pinfunction "1_1") (pintype "passive"))
      (node (ref "MEAS") (pin "3") (pinfunction "1_3") (pintype "passive"))
    )
    (net (code "57") (name "Net-(J8-+)") (class "Default")
      (node (ref "J8") (pin "2") (pinfunction "+_2") (pintype "bidirectional"))
      (node (ref "MEAS1") (pin "1") (pinfunction "1_1") (pintype "passive"))
      (node (ref "MEAS1") (pin "3") (pinfunction "1_3") (pintype "passive"))
    )
    (net (code "58") (name "Net-(Q2A-B)") (class "Default")
      (node (ref "Q2") (pin "5") (pinfunction "B_5") (pintype "passive"))
      (node (ref "R23") (pin "2") (pinfunction "2_2") (pintype "passive"))
    )
    (net (code "59") (name "Net-(Q2A-E)") (class "Default")
      (node (ref "Q2") (pin "4") (pinfunction "E_4") (pintype "passive"))
      (node (ref "R29") (pin "1") (pinfunction "1_1") (pintype "passive"))
      (node (ref "U6") (pin "14") (pinfunction "~{RTS}_14") (pintype "bidirectional"))
    )
    (net (code "60") (name "Net-(Q2B-B)") (class "Default")
      (node (ref "Q2") (pin "2") (pinfunction "B_2") (pintype "passive"))
      (node (ref "R29") (pin "2") (pinfunction "2_2") (pintype "passive"))
    )
    (net (code "61") (name "Net-(Q2B-E)") (class "Default")
      (node (ref "Q2") (pin "1") (pinfunction "E_1") (pintype "passive"))
      (node (ref "R23") (pin "1") (pinfunction "1_1") (pintype "passive"))
      (node (ref "U6") (pin "13") (pinfunction "~{DTR}_13") (pintype "bidirectional"))
    )
    (net (code "62") (name "Net-(R2A-1)") (class "Default")
      (node (ref "R2") (pin "P1") (pinfunction "1_P1") (pintype "passive"))
      (node (ref "U3") (pin "53") (pinfunction "TIMEPULSE_53") (pintype "bidirectional"))
    )
    (net (code "63") (name "Net-(R2C-1)") (class "Default")
      (node (ref "R2") (pin "P3") (pinfunction "1_P3") (pintype "passive"))
      (node (ref "U3") (pin "50") (pinfunction "~{SAFEBOOT}_50") (pintype "bidirectional"))
    )
    (net (code "64") (name "Net-(R2D-1)") (class "Default")
      (node (ref "R2") (pin "P4") (pinfunction "1_P4") (pintype "passive"))
      (node (ref "U3") (pin "49") (pinfunction "~{RESET}_49") (pintype "bidirectional"))
    )
    (net (code "65") (name "Net-(R4A-2)") (class "Default")
      (node (ref "R4") (pin "P8") (pinfunction "2_P8") (pintype "passive"))
      (node (ref "U3") (pin "19") (pinfunction "GEO_STAT_19") (pintype "bidirectional"))
    )
    (net (code "66") (name "Net-(R4B-2)") (class "Default")
      (node (ref "R4") (pin "P7") (pinfunction "2_P7") (pintype "passive"))
      (node (ref "U3") (pin "20") (pinfunction "RTK_STAT_20") (pintype "bidirectional"))
    )
    (net (code "67") (name "Net-(R4C-2)") (class "Default")
      (node (ref "R4") (pin "P6") (pinfunction "2_P6") (pintype "passive"))
      (node (ref "U3") (pin "26") (pinfunction "RX2_26") (pintype "bidirectional"))
    )
    (net (code "68") (name "Net-(R4D-2)") (class "Default")
      (node (ref "R4") (pin "P5") (pinfunction "2_P5") (pintype "passive"))
      (node (ref "U3") (pin "27") (pinfunction "TX2_27") (pintype "bidirectional"))
    )
    (net (code "69") (name "Net-(R9A-1)") (class "Default")
      (node (ref "R9") (pin "P1") (pinfunction "1_P1") (pintype "passive"))
      (node (ref "U3") (pin "46") (pinfunction "TX_READY_46") (pintype "bidirectional"))
    )
    (net (code "70") (name "Net-(R9B-1)") (class "Default")
      (node (ref "R9") (pin "P2") (pinfunction "1_P2") (pintype "passive"))
      (node (ref "U3") (pin "45") (pinfunction "SCL/CLK_45") (pintype "bidirectional"))
    )
    (net (code "71") (name "Net-(R9C-1)") (class "Default")
      (node (ref "R9") (pin "P3") (pinfunction "1_P3") (pintype "passive"))
      (node (ref "U3") (pin "44") (pinfunction "SDA/~{CS}_44") (pintype "bidirectional"))
    )
    (net (code "72") (name "Net-(R9D-1)") (class "Default")
      (node (ref "R9") (pin "P4") (pinfunction "1_P4") (pintype "passive"))
      (node (ref "U3") (pin "43") (pinfunction "RX/MOSI_43") (pintype "bidirectional"))
    )
    (net (code "73") (name "Net-(U1-PROG)") (class "Default")
      (node (ref "R7") (pin "2") (pinfunction "2_2") (pintype "passive"))
      (node (ref "U1") (pin "5") (pinfunction "PROG_5") (pintype "input"))
    )
    (net (code "74") (name "Net-(U3-TX{slash}MISO)") (class "Default")
      (node (ref "R3") (pin "1") (pinfunction "1_1") (pintype "passive"))
      (node (ref "U3") (pin "42") (pinfunction "TX/MISO_42") (pintype "bidirectional"))
    )
    (net (code "75") (name "Net-(U3-USB_D+)") (class "Default")
      (node (ref "R27") (pin "2") (pinfunction "2_2") (pintype "passive"))
      (node (ref "U3") (pin "40") (pinfunction "USB_D+_40") (pintype "bidirectional"))
    )
    (net (code "76") (name "Net-(U3-USB_D-)") (class "Default")
      (node (ref "R28") (pin "2") (pinfunction "2_2") (pintype "passive"))
      (node (ref "U3") (pin "39") (pinfunction "USB_D-_39") (pintype "bidirectional"))
    )
    (net (code "77") (name "Net-(U3-V_RF)") (class "Default")
      (node (ref "R14") (pin "2") (pinfunction "2_2") (pintype "passive"))
      (node (ref "U3") (pin "7") (pinfunction "V_RF_7") (pintype "bidirectional"))
    )
    (net (code "78") (name "Net-(U6-UD+)") (class "Default")
      (node (ref "J3") (pin "A6") (pinfunction "D+_A6") (pintype "bidirectional"))
      (node (ref "J3") (pin "B6") (pinfunction "D+_B6") (pintype "bidirectional"))
      (node (ref "U6") (pin "5") (pinfunction "UD+_5") (pintype "bidirectional"))
    )
    (net (code "79") (name "Net-(U6-UD-)") (class "Default")
      (node (ref "J3") (pin "A7") (pinfunction "D-_A7") (pintype "bidirectional"))
      (node (ref "J3") (pin "B7") (pinfunction "D-_B7") (pintype "bidirectional"))
      (node (ref "U6") (pin "6") (pinfunction "UD-_6") (pintype "bidirectional"))
    )
    (net (code "80") (name "VIN") (class "Default")
      (node (ref "C9") (pin "1") (pinfunction "1_1") (pintype "passive"))
      (node (ref "D13") (pin "4") (pinfunction "A_4") (pintype "bidirectional"))
      (node (ref "D6") (pin "5") (pinfunction "5_5") (pintype "bidirectional"))
      (node (ref "D7") (pin "C") (pinfunction "C_C") (pintype "passive"))
      (node (ref "D9") (pin "C") (pinfunction "C_C") (pintype "passive"))
      (node (ref "J7") (pin "2") (pinfunction "1_2") (pintype "passive"))
      (node (ref "MEAS") (pin "2") (pinfunction "2_2") (pintype "passive"))
      (node (ref "MEAS") (pin "4") (pinfunction "2_4") (pintype "passive"))
      (node (ref "U1") (pin "4") (pinfunction "VIN_4") (pintype "power_in"))
    )
    (net (code "81") (name "V_BATT") (class "Default")
      (node (ref "C15") (pin "1") (pinfunction "1_1") (pintype "passive"))
      (node (ref "C8") (pin "1") (pinfunction "1_1") (pintype "passive"))
      (node (ref "D7") (pin "A") (pinfunction "A_A") (pintype "passive"))
      (node (ref "J10") (pin "1") (pinfunction "1_1") (pintype "passive"))
      (node (ref "MEAS1") (pin "2") (pinfunction "2_2") (pintype "passive"))
      (node (ref "MEAS1") (pin "4") (pinfunction "2_4") (pintype "passive"))
      (node (ref "U1") (pin "3") (pinfunction "VBAT_3") (pintype "power_in"))
      (node (ref "U7") (pin "2") (pinfunction "CELL_2") (pintype "input"))
      (node (ref "U7") (pin "3") (pinfunction "VDD_3") (pintype "bidirectional"))
    )
    (net (code "82") (name "ZED-RXI1") (class "Default")
      (node (ref "J15") (pin "2") (pinfunction "2_2") (pintype "passive"))
      (node (ref "R9") (pin "P5") (pinfunction "2_P5") (pintype "passive"))
      (node (ref "SERIAL1_CONNECTION") (pin "2") (pinfunction "2_2") (pintype "bidirectional"))
    )
    (net (code "83") (name "ZED-RXI2") (class "Default")
      (node (ref "BLUETOOTH_BROADCAST") (pin "3") (pinfunction "3_3") (pintype "bidirectional"))
      (node (ref "J11") (pin "2") (pinfunction "2_2") (pintype "passive"))
      (node (ref "J9") (pin "3") (pinfunction "3_3") (pintype "passive"))
      (node (ref "R4") (pin "P3") (pinfunction "1_P3") (pintype "passive"))
    )
    (net (code "84") (name "ZED-TXO1") (class "Default")
      (node (ref "J15") (pin "1") (pinfunction "1_1") (pintype "passive"))
      (node (ref "R3") (pin "2") (pinfunction "2_2") (pintype "passive"))
      (node (ref "SERIAL1_CONNECTION") (pin "5") (pinfunction "5_5") (pintype "bidirectional"))
    )
    (net (code "85") (name "ZED-TXO2") (class "Default")
      (node (ref "BLUETOOTH_BROADCAST") (pin "6") (pinfunction "6_6") (pintype "bidirectional"))
      (node (ref "J11") (pin "3") (pinfunction "3_3") (pintype "passive"))
      (node (ref "J9") (pin "2") (pinfunction "2_2") (pintype "passive"))
      (node (ref "R4") (pin "P4") (pinfunction "1_P4") (pintype "passive"))
    )
    (net (code "86") (name "ZED_FENCE_STAT") (class "Default")
      (node (ref "J1") (pin "2") (pinfunction "2_2") (pintype "passive"))
      (node (ref "R4") (pin "P1") (pinfunction "1_P1") (pintype "passive"))
    )
    (net (code "87") (name "ZED_PPS_STAT") (class "Default")
      (node (ref "J13") (pin "1") (pinfunction "1_1") (pintype "passive"))
      (node (ref "R11") (pin "2") (pinfunction "2_2") (pintype "passive"))
      (node (ref "R2") (pin "P8") (pinfunction "2_P8") (pintype "passive"))
    )
    (net (code "88") (name "ZED_RTK_STAT") (class "Default")
      (node (ref "D3") (pin "C") (pinfunction "C_C") (pintype "passive"))
      (node (ref "J1") (pin "3") (pinfunction "3_3") (pintype "passive"))
      (node (ref "R4") (pin "P2") (pinfunction "1_P2") (pintype "passive"))
    )
    (net (code "89") (name "ZED_~{SAFE}") (class "Default")
      (node (ref "J13") (pin "2") (pinfunction "2_2") (pintype "passive"))
      (node (ref "R2") (pin "P6") (pinfunction "2_P6") (pintype "passive"))
    )
    (net (code "90") (name "unconnected-(J8-PAD1-PadNC1)") (class "Default")
      (node (ref "J8") (pin "NC1") (pinfunction "PAD1_NC1") (pintype "bidirectional"))
    )
    (net (code "91") (name "unconnected-(J8-PAD2-PadNC2)") (class "Default")
      (node (ref "J8") (pin "NC2") (pinfunction "PAD2_NC2") (pintype "bidirectional"))
    )
    (net (code "92") (name "unconnected-(J16-DAT1{slash}NC-PadDAT1)") (class "Default")
      (node (ref "J16") (pin "DAT1") (pinfunction "DAT1/NC_DAT1") (pintype "bidirectional"))
    )
    (net (code "93") (name "unconnected-(J16-DAT2{slash}NC-PadDAT2)") (class "Default")
      (node (ref "J16") (pin "DAT2") (pinfunction "DAT2/NC_DAT2") (pintype "bidirectional"))
    )
    (net (code "94") (name "unconnected-(R2B-1-PadP2)") (class "Default")
      (node (ref "R2") (pin "P2") (pinfunction "1_P2") (pintype "passive"))
    )
    (net (code "95") (name "unconnected-(R2B-2-PadP7)") (class "Default")
      (node (ref "R2") (pin "P7") (pinfunction "2_P7") (pintype "passive"))
    )
    (net (code "96") (name "unconnected-(U2-NC-Pad4)") (class "Default")
      (node (ref "U2") (pin "4") (pinfunction "NC_4") (pintype "no_connect"))
    )
    (net (code "97") (name "unconnected-(U3-ANT_DETECT-Pad4)") (class "Default")
      (node (ref "U3") (pin "4") (pinfunction "ANT_DETECT_4") (pintype "bidirectional"))
    )
    (net (code "98") (name "unconnected-(U3-ANT_OFF-Pad5)") (class "Default")
      (node (ref "U3") (pin "5") (pinfunction "ANT_OFF_5") (pintype "bidirectional"))
    )
    (net (code "99") (name "unconnected-(U3-D_SEL-Pad47)") (class "Default")
      (node (ref "U3") (pin "47") (pinfunction "D_SEL_47") (pintype "bidirectional"))
    )
    (net (code "100") (name "unconnected-(U3-EXTINT-Pad51)") (class "Default")
      (node (ref "U3") (pin "51") (pinfunction "EXTINT_51") (pintype "bidirectional"))
    )
    (net (code "101") (name "unconnected-(U3-~{ANT_SHORT}-Pad6)") (class "Default")
      (node (ref "U3") (pin "6") (pinfunction "~{ANT_SHORT}_6") (pintype "bidirectional"))
    )
    (net (code "102") (name "unconnected-(U5-SCK{slash}IO6-Pad20)") (class "Default")
      (node (ref "U5") (pin "20") (pinfunction "SCK/IO6_20") (pintype "bidirectional"))
    )
    (net (code "103") (name "unconnected-(U5-SCS{slash}IO11-Pad19)") (class "Default")
      (node (ref "U5") (pin "19") (pinfunction "SCS/IO11_19") (pintype "bidirectional"))
    )
    (net (code "104") (name "unconnected-(U5-SDI{slash}IO8-Pad22)") (class "Default")
      (node (ref "U5") (pin "22") (pinfunction "SDI/IO8_22") (pintype "bidirectional"))
    )
    (net (code "105") (name "unconnected-(U5-SDO{slash}IO7-Pad21)") (class "Default")
      (node (ref "U5") (pin "21") (pinfunction "SDO/IO7_21") (pintype "bidirectional"))
    )
    (net (code "106") (name "unconnected-(U5-SHD{slash}IO9-Pad17)") (class "Default")
      (node (ref "U5") (pin "17") (pinfunction "SHD/IO9_17") (pintype "bidirectional"))
    )
    (net (code "107") (name "unconnected-(U5-SWP{slash}IO10-Pad18)") (class "Default")
      (node (ref "U5") (pin "18") (pinfunction "SWP/IO10_18") (pintype "bidirectional"))
    )
    (net (code "108") (name "unconnected-(U6-R232-Pad15)") (class "Default")
      (node (ref "U6") (pin "15") (pinfunction "R232_15") (pintype "bidirectional"))
    )
    (net (code "109") (name "unconnected-(U6-~{CTS}-Pad9)") (class "Default")
      (node (ref "U6") (pin "9") (pinfunction "~{CTS}_9") (pintype "bidirectional"))
    )
    (net (code "110") (name "unconnected-(U6-~{DCD}-Pad12)") (class "Default")
      (node (ref "U6") (pin "12") (pinfunction "~{DCD}_12") (pintype "bidirectional"))
    )
    (net (code "111") (name "unconnected-(U6-~{DSR}-Pad10)") (class "Default")
      (node (ref "U6") (pin "10") (pinfunction "~{DSR}_10") (pintype "bidirectional"))
    )
    (net (code "112") (name "unconnected-(U6-~{RI}-Pad11)") (class "Default")
      (node (ref "U6") (pin "11") (pinfunction "~{RI}_11") (pintype "bidirectional"))
    )
  )
)
